# Segger_JTAG_and_Boundary_Scan_v1p3.net
KiCad netlist of a schematic drawn in EAGLE
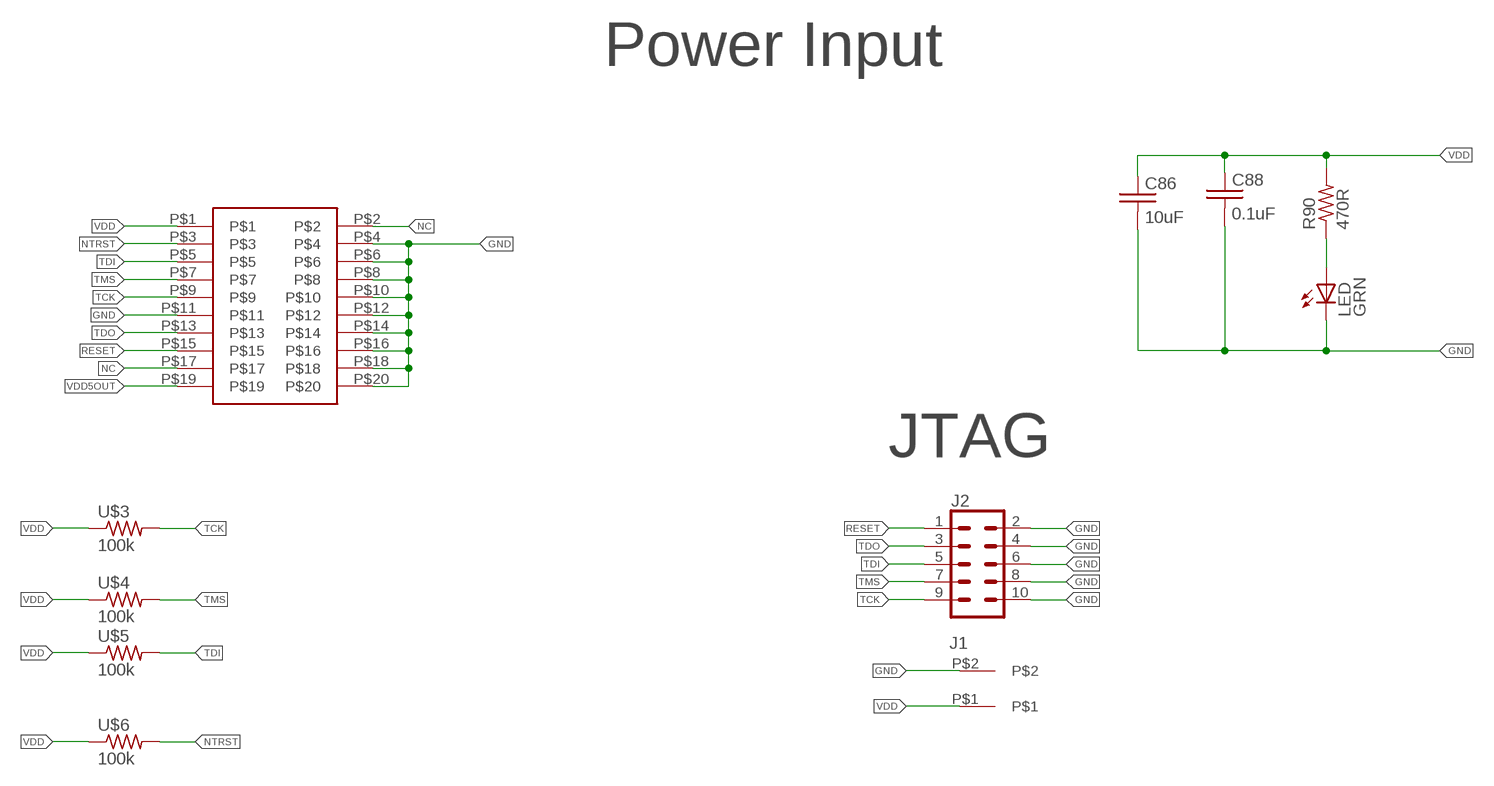
[diagram p0: schematic, sheet 1]

(export (version "E")
  (design (tool "Eeschema 10.0.6"))
  (components
    (comp (ref "C86")
      (value "10uF")
      (footprint "eagle-import:0805")
      (libsource (lib "eagle-import") (part "C_0805"))
    )
    (comp (ref "C88")
      (value "0.1uF")
      (footprint "eagle-import:0805")
      (libsource (lib "eagle-import") (part "C_0805"))
    )
    (comp (ref "J1")
      (value "2-pos")
      (footprint "eagle-import:2_3.81MM_PITCH")
      (fields (field (name "PARTNO") "691322310002"))
      (libsource (lib "eagle-import") (part "3.81MM_1_X_2_RT_ANGLE_PLUG_HEADER"))
    )
    (comp (ref "J2")
      (value "CONN_05X2PTH")
      (footprint "eagle-import:2X5")
      (libsource (lib "eagle-import") (part "CONN_05X2PTH"))
    )
    (comp (ref "LED")
      (value "LED_0805_GREEN")
      (footprint "eagle-import:LED_0805_GREEN")
      (libsource (lib "eagle-import") (part "LED_0805_GREEN"))
    )
    (comp (ref "R90")
      (value "470R")
      (footprint "eagle-import:0805")
      (libsource (lib "eagle-import") (part "R_0805"))
    )
    (comp (ref "U$2")
      (value "2_X_10_HEADER_GENERIC")
      (footprint "eagle-import:2_X_10_.1_INCH")
      (libsource (lib "eagle-import") (part "2_X_10_HEADER_GENERIC"))
    )
    (comp (ref "U$3")
      (value "100k")
      (footprint "eagle-import:0805")
      (libsource (lib "eagle-import") (part "R_0805"))
    )
    (comp (ref "U$4")
      (value "100k")
      (footprint "eagle-import:0805")
      (libsource (lib "eagle-import") (part "R_0805"))
    )
    (comp (ref "U$5")
      (value "100k")
      (footprint "eagle-import:0805")
      (libsource (lib "eagle-import") (part "R_0805"))
    )
    (comp (ref "U$6")
      (value "100k")
      (footprint "eagle-import:0805")
      (libsource (lib "eagle-import") (part "R_0805"))
    )
  )
  (nets
    (net (code "1") (name "GND") (class "Default")
      (node (ref "C86") (pin "2") (pinfunction "2_2") (pintype "passive"))
      (node (ref "C88") (pin "2") (pinfunction "2_2") (pintype "passive"))
      (node (ref "J1") (pin "P$2") (pinfunction "P$2_P$2") (pintype "bidirectional"))
      (node (ref "J2") (pin "10") (pinfunction "10_10") (pintype "passive"))
      (node (ref "J2") (pin "2") (pinfunction "2_2") (pintype "passive"))
      (node (ref "J2") (pin "4") (pinfunction "4_4") (pintype "passive"))
      (node (ref "J2") (pin "6") (pinfunction "6_6") (pintype "passive"))
      (node (ref "J2") (pin "8") (pinfunction "8_8") (pintype "passive"))
      (node (ref "LED") (pin "C") (pinfunction "C_C") (pintype "passive"))
      (node (ref "U$2") (pin "P$10") (pinfunction "P$10_P$10") (pintype "bidirectional"))
      (node (ref "U$2") (pin "P$11") (pinfunction "P$11_P$11") (pintype "bidirectional"))
      (node (ref "U$2") (pin "P$12") (pinfunction "P$12_P$12") (pintype "bidirectional"))
      (node (ref "U$2") (pin "P$14") (pinfunction "P$14_P$14") (pintype "bidirectional"))
      (node (ref "U$2") (pin "P$16") (pinfunction "P$16_P$16") (pintype "bidirectional"))
      (node (ref "U$2") (pin "P$18") (pinfunction "P$18_P$18") (pintype "bidirectional"))
      (node (ref "U$2") (pin "P$20") (pinfunction "P$20_P$20") (pintype "bidirectional"))
      (node (ref "U$2") (pin "P$4") (pinfunction "P$4_P$4") (pintype "bidirectional"))
      (node (ref "U$2") (pin "P$6") (pinfunction "P$6_P$6") (pintype "bidirectional"))
      (node (ref "U$2") (pin "P$8") (pinfunction "P$8_P$8") (pintype "bidirectional"))
    )
    (net (code "2") (name "NC") (class "Default")
      (node (ref "U$2") (pin "P$17") (pinfunction "P$17_P$17") (pintype "bidirectional"))
      (node (ref "U$2") (pin "P$2") (pinfunction "P$2_P$2") (pintype "bidirectional"))
    )
    (net (code "3") (name "NTRST") (class "Default")
      (node (ref "U$2") (pin "P$3") (pinfunction "P$3_P$3") (pintype "bidirectional"))
      (node (ref "U$6") (pin "2") (pinfunction "2_2") (pintype "passive"))
    )
    (net (code "4") (name "Net-(LED-PadA)") (class "Default")
      (node (ref "LED") (pin "A") (pinfunction "A_A") (pintype "passive"))
      (node (ref "R90") (pin "1") (pinfunction "1_1") (pintype "passive"))
    )
    (net (code "5") (name "RESET") (class "Default")
      (node (ref "J2") (pin "1") (pinfunction "1_1") (pintype "passive"))
      (node (ref "U$2") (pin "P$15") (pinfunction "P$15_P$15") (pintype "bidirectional"))
    )
    (net (code "6") (name "TCK") (class "Default")
      (node (ref "J2") (pin "9") (pinfunction "9_9") (pintype "passive"))
      (node (ref "U$2") (pin "P$9") (pinfunction "P$9_P$9") (pintype "bidirectional"))
      (node (ref "U$3") (pin "2") (pinfunction "2_2") (pintype "passive"))
    )
    (net (code "7") (name "TDI") (class "Default")
      (node (ref "J2") (pin "5") (pinfunction "5_5") (pintype "passive"))
      (node (ref "U$2") (pin "P$5") (pinfunction "P$5_P$5") (pintype "bidirectional"))
      (node (ref "U$5") (pin "2") (pinfunction "2_2") (pintype "passive"))
    )
    (net (code "8") (name "TDO") (class "Default")
      (node (ref "J2") (pin "3") (pinfunction "3_3") (pintype "passive"))
      (node (ref "U$2") (pin "P$13") (pinfunction "P$13_P$13") (pintype "bidirectional"))
    )
    (net (code "9") (name "TMS") (class "Default")
      (node (ref "J2") (pin "7") (pinfunction "7_7") (pintype "passive"))
      (node (ref "U$2") (pin "P$7") (pinfunction "P$7_P$7") (pintype "bidirectional"))
      (node (ref "U$4") (pin "2") (pinfunction "2_2") (pintype "passive"))
    )
    (net (code "10") (name "VDD") (class "Default")
      (node (ref "C86") (pin "1") (pinfunction "1_1") (pintype "passive"))
      (node (ref "C88") (pin "1") (pinfunction "1_1") (pintype "passive"))
      (node (ref "J1") (pin "P$1") (pinfunction "P$1_P$1") (pintype "bidirectional"))
      (node (ref "R90") (pin "2") (pinfunction "2_2") (pintype "passive"))
      (node (ref "U$2") (pin "P$1") (pinfunction "P$1_P$1") (pintype "bidirectional"))
      (node (ref "U$3") (pin "1") (pinfunction "1_1") (pintype "passive"))
      (node (ref "U$4") (pin "1") (pinfunction "1_1") (pintype "passive"))
      (node (ref "U$5") (pin "1") (pinfunction "1_1") (pintype "passive"))
      (node (ref "U$6") (pin "1") (pinfunction "1_1") (pintype "passive"))
    )
    (net (code "11") (name "VDD5OUT") (class "Default")
      (node (ref "U$2") (pin "P$19") (pinfunction "P$19_P$19") (pintype "bidirectional"))
    )
  )
)
